# DDW_sch.net
KiCad netlist of a schematic drawn in Altium Designer
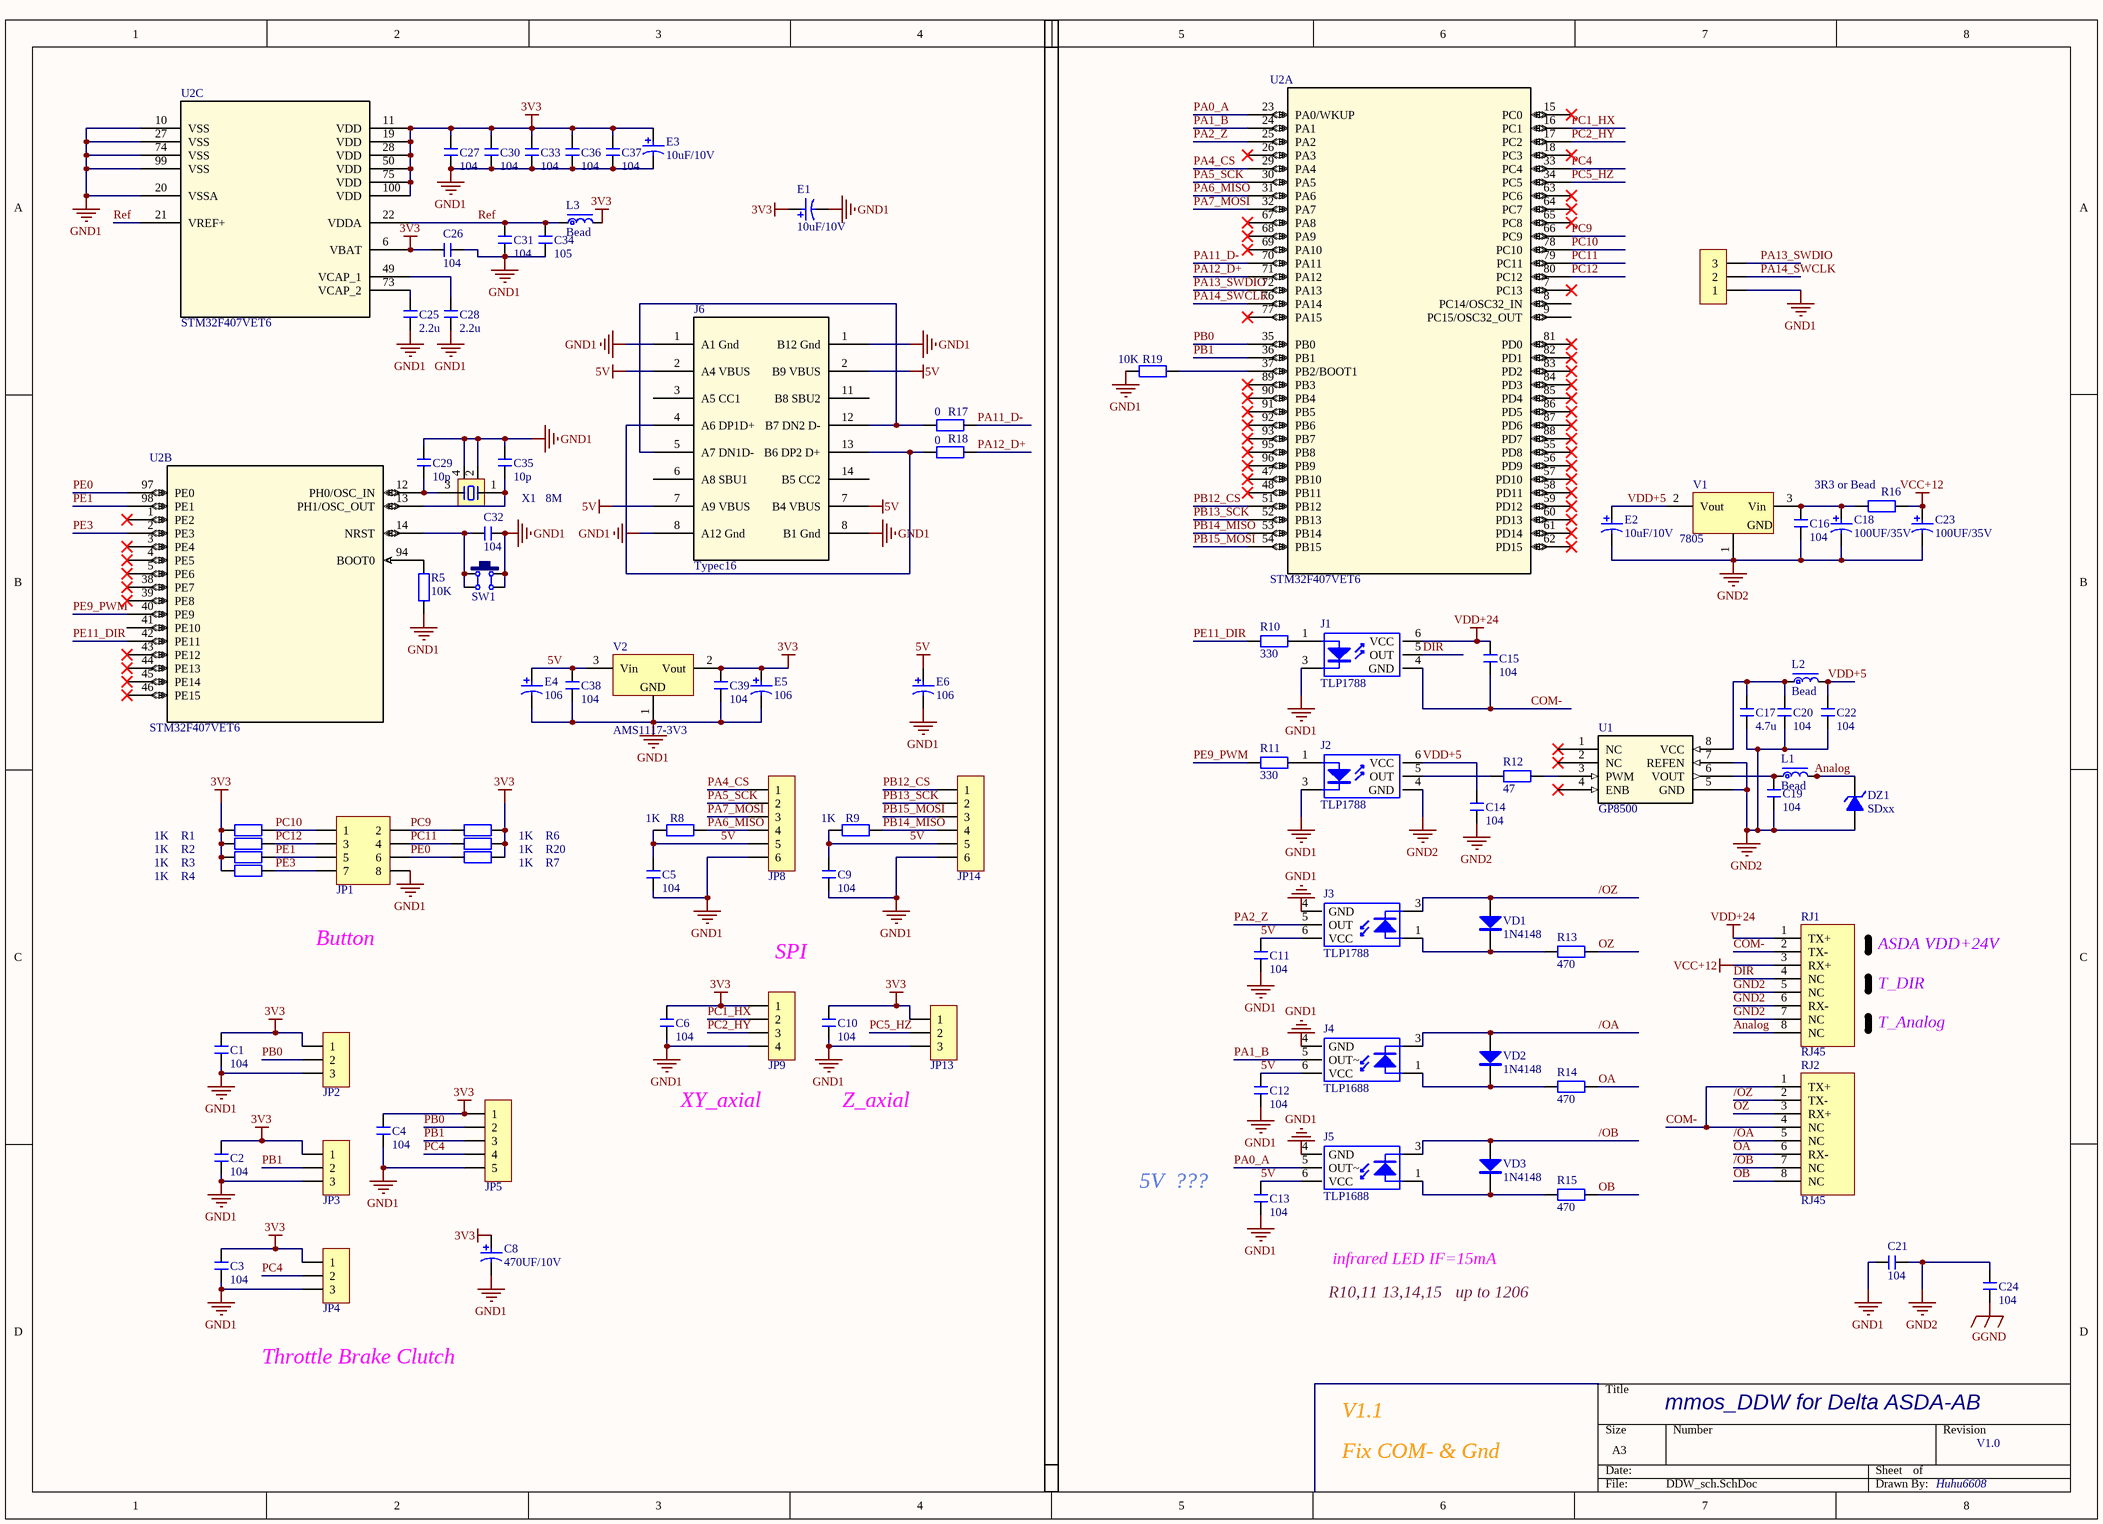
[diagram p0: DDW_sch.SchDoc]

(export (version "E")
  (design (tool "Eeschema 10.0.6"))
  (components
    (comp (ref "C1")
      (value "104")
      (footprint "C 0603")
      (description "瓷片电容-贴片")
      (libsource (lib "A") (part "Cap-CER-SMD"))
    )
    (comp (ref "C2")
      (value "104")
      (footprint "C 0603")
      (description "瓷片电容-贴片")
      (libsource (lib "A") (part "Cap-CER-SMD"))
    )
    (comp (ref "C3")
      (value "104")
      (footprint "C 0603")
      (description "瓷片电容-贴片")
      (libsource (lib "A") (part "Cap-CER-SMD"))
    )
    (comp (ref "C4")
      (value "104")
      (footprint "C 0603")
      (description "瓷片电容-贴片")
      (libsource (lib "A") (part "Cap-CER-SMD"))
    )
    (comp (ref "C5")
      (value "104")
      (footprint "C 0603")
      (description "瓷片电容-贴片")
      (libsource (lib "A") (part "Cap-CER-SMD"))
    )
    (comp (ref "C6")
      (value "104")
      (footprint "C 0603")
      (description "瓷片电容-贴片")
      (libsource (lib "A") (part "Cap-CER-SMD"))
    )
    (comp (ref "C8")
      (value "470UF/10V")
      (footprint "CAP 2.5*6.3*11.2")
      (description "铝电解电容-直插")
      (libsource (lib "A") (part "Cap-AE-RAD"))
    )
    (comp (ref "C9")
      (value "104")
      (footprint "C 0603")
      (description "瓷片电容-贴片")
      (libsource (lib "A") (part "Cap-CER-SMD"))
    )
    (comp (ref "C10")
      (value "104")
      (footprint "C 0603")
      (description "瓷片电容-贴片")
      (libsource (lib "A") (part "Cap-CER-SMD"))
    )
    (comp (ref "C11")
      (value "104")
      (footprint "C 0603")
      (description "瓷片电容-贴片")
      (libsource (lib "A") (part "Cap-CER-SMD"))
    )
    (comp (ref "C12")
      (value "104")
      (footprint "C 0603")
      (description "瓷片电容-贴片")
      (libsource (lib "A") (part "Cap-CER-SMD"))
    )
    (comp (ref "C13")
      (value "104")
      (footprint "C 0603")
      (description "瓷片电容-贴片")
      (libsource (lib "A") (part "Cap-CER-SMD"))
    )
    (comp (ref "C14")
      (value "104")
      (footprint "C 0603")
      (description "瓷片电容-贴片")
      (libsource (lib "A") (part "Cap-CER-SMD"))
    )
    (comp (ref "C15")
      (value "104")
      (footprint "C 0603")
      (description "瓷片电容-贴片")
      (libsource (lib "A") (part "Cap-CER-SMD"))
    )
    (comp (ref "C16")
      (value "104")
      (footprint "C 0603")
      (description "瓷片电容-贴片")
      (libsource (lib "A") (part "Cap-CER-SMD"))
    )
    (comp (ref "C17")
      (value "4.7u")
      (footprint "C 0603")
      (description "瓷片电容-贴片")
      (libsource (lib "A") (part "Cap-CER-SMD"))
    )
    (comp (ref "C18")
      (value "100UF/35V")
      (footprint "CAP 2.5*6.3*11.2")
      (description "铝电解电容-直插")
      (libsource (lib "A") (part "Cap-AE-RAD"))
    )
    (comp (ref "C19")
      (value "104")
      (footprint "C 0603")
      (description "瓷片电容-贴片")
      (libsource (lib "A") (part "Cap-CER-SMD"))
    )
    (comp (ref "C20")
      (value "104")
      (footprint "C 0603")
      (description "瓷片电容-贴片")
      (libsource (lib "A") (part "Cap-CER-SMD"))
    )
    (comp (ref "C21")
      (value "104")
      (footprint "Y")
      (description "瓷片电容-贴片")
      (libsource (lib "A") (part "Cap-CER-SMD"))
    )
    (comp (ref "C22")
      (value "104")
      (footprint "C 0603")
      (description "瓷片电容-贴片")
      (libsource (lib "A") (part "Cap-CER-SMD"))
    )
    (comp (ref "C23")
      (value "100UF/35V")
      (footprint "CAP 2.5*6.3*11.2")
      (description "铝电解电容-直插")
      (libsource (lib "A") (part "Cap-AE-RAD"))
    )
    (comp (ref "C24")
      (value "104")
      (footprint "Y")
      (description "瓷片电容-贴片")
      (libsource (lib "A") (part "Cap-CER-SMD"))
    )
    (comp (ref "C25")
      (value "2.2u")
      (footprint "C 0603")
      (description "瓷片电容-贴片")
      (libsource (lib "A") (part "Cap-CER-SMD"))
    )
    (comp (ref "C26")
      (value "104")
      (footprint "C 0603")
      (description "瓷片电容-贴片")
      (libsource (lib "A") (part "Cap-CER-SMD"))
    )
    (comp (ref "C27")
      (value "104")
      (footprint "C 0603")
      (description "瓷片电容-贴片")
      (libsource (lib "A") (part "Cap-CER-SMD"))
    )
    (comp (ref "C28")
      (value "2.2u")
      (footprint "C 0603")
      (description "瓷片电容-贴片")
      (libsource (lib "A") (part "Cap-CER-SMD"))
    )
    (comp (ref "C29")
      (value "10p")
      (footprint "C 0603")
      (description "瓷片电容-贴片")
      (libsource (lib "A") (part "Cap-CER-SMD"))
    )
    (comp (ref "C30")
      (value "104")
      (footprint "C 0603")
      (description "瓷片电容-贴片")
      (libsource (lib "A") (part "Cap-CER-SMD"))
    )
    (comp (ref "C31")
      (value "104")
      (footprint "C 0603")
      (description "瓷片电容-贴片")
      (libsource (lib "A") (part "Cap-CER-SMD"))
    )
    (comp (ref "C32")
      (value "104")
      (footprint "C 0603")
      (description "瓷片电容-贴片")
      (libsource (lib "A") (part "Cap-CER-SMD"))
    )
    (comp (ref "C33")
      (value "104")
      (footprint "C 0603")
      (description "瓷片电容-贴片")
      (libsource (lib "A") (part "Cap-CER-SMD"))
    )
    (comp (ref "C34")
      (value "105")
      (footprint "C 0603")
      (description "瓷片电容-贴片")
      (libsource (lib "A") (part "Cap-CER-SMD"))
    )
    (comp (ref "C35")
      (value "10p")
      (footprint "C 0603")
      (description "瓷片电容-贴片")
      (libsource (lib "A") (part "Cap-CER-SMD"))
    )
    (comp (ref "C36")
      (value "104")
      (footprint "C 0603")
      (description "瓷片电容-贴片")
      (libsource (lib "A") (part "Cap-CER-SMD"))
    )
    (comp (ref "C37")
      (value "104")
      (footprint "C 0603")
      (description "瓷片电容-贴片")
      (libsource (lib "A") (part "Cap-CER-SMD"))
    )
    (comp (ref "C38")
      (value "104")
      (footprint "C 0603")
      (description "瓷片电容-贴片")
      (libsource (lib "A") (part "Cap-CER-SMD"))
    )
    (comp (ref "C39")
      (value "104")
      (footprint "C 0603")
      (description "瓷片电容-贴片")
      (libsource (lib "A") (part "Cap-CER-SMD"))
    )
    (comp (ref "DZ1")
      (value "SDxx")
      (footprint "SOD-323")
      (description "TVS")
      (fields (field (name "版权归属") "源创客"))
      (libsource (lib "A") (part "SDxx"))
    )
    (comp (ref "E1")
      (value "10uF/10V")
      (footprint "CD B(3528)")
      (description "钽电解电容-贴片")
      (libsource (lib "A") (part "Cap-TAN-SMD"))
    )
    (comp (ref "E2")
      (value "10uF/10V")
      (footprint "CD B(3528)")
      (description "钽电解电容-贴片")
      (libsource (lib "A") (part "Cap-TAN-SMD"))
    )
    (comp (ref "E3")
      (value "10uF/10V")
      (footprint "CD B(3528)")
      (description "钽电解电容-贴片")
      (libsource (lib "A") (part "Cap-TAN-SMD"))
    )
    (comp (ref "E4")
      (value "106")
      (footprint "CD B(3528)")
      (description "钽电解电容-贴片")
      (libsource (lib "A") (part "Cap-TAN-SMD"))
    )
    (comp (ref "E5")
      (value "106")
      (footprint "CD B(3528)")
      (description "钽电解电容-贴片")
      (libsource (lib "A") (part "Cap-TAN-SMD"))
    )
    (comp (ref "E6")
      (value "106")
      (footprint "CD B(3528)")
      (description "钽电解电容-贴片")
      (libsource (lib "A") (part "Cap-TAN-SMD"))
    )
    (comp (ref "J1")
      (value "TLP1788")
      (footprint "SOP5")
      (description "光耦")
      (fields (field (name "版权归属") "源创客"))
      (libsource (lib "A") (part "TLP1788"))
    )
    (comp (ref "J2")
      (value "TLP1788")
      (footprint "SOP5")
      (description "光耦")
      (fields (field (name "版权归属") "源创客"))
      (libsource (lib "A") (part "TLP1788"))
    )
    (comp (ref "J3")
      (value "TLP1788")
      (footprint "SOP5")
      (description "光耦")
      (fields (field (name "版权归属") "源创客"))
      (libsource (lib "Miscellaneous Devices") (part "TLP1788"))
    )
    (comp (ref "J4")
      (value "TLP1688")
      (footprint "SOP5")
      (description "光耦")
      (fields (field (name "版权归属") "源创客"))
      (libsource (lib "A") (part "TLP1688"))
    )
    (comp (ref "J5")
      (value "TLP1688")
      (footprint "SOP5")
      (description "光耦")
      (fields (field (name "版权归属") "源创客"))
      (libsource (lib "A") (part "TLP1688"))
    )
    (comp (ref "J6") (value "Typec16") (footprint "typec 16p") (libsource (lib "A") (part "Typec16")))
    (comp (ref "JP1")
      (value "Header 4X2")
      (footprint "HDR-4X2")
      (description "4*2P接插件")
      (fields (field (name "版权归属") "源创客"))
      (libsource (lib "A") (part "Header 4X2"))
    )
    (comp (ref "JP2")
      (value "HDR-1X3")
      (footprint "HDR-1X3")
      (description "3P接插件")
      (fields (field (name "版权归属") "源创客"))
      (libsource (lib "A") (part "Header 3"))
    )
    (comp (ref "JP3")
      (value "HDR-1X3")
      (footprint "HDR-1X3")
      (description "3P接插件")
      (fields (field (name "版权归属") "源创客"))
      (libsource (lib "A") (part "Header 3"))
    )
    (comp (ref "JP4")
      (value "HDR-1X3")
      (footprint "HDR-1X3")
      (description "3P接插件")
      (fields (field (name "版权归属") "源创客"))
      (libsource (lib "A") (part "Header 3"))
    )
    (comp (ref "JP5")
      (value "HDR-1X5")
      (footprint "HDR-1X5")
      (description "5P接插件")
      (fields (field (name "版权归属") "源创客"))
      (libsource (lib "A") (part "Header 5"))
    )
    (comp (ref "JP6")
      (value "HDR-1X3")
      (footprint "HDR-1X3")
      (description "3P接插件")
      (fields (field (name "版权归属") "源创客"))
      (libsource (lib "") (part "Header 3_1"))
    )
    (comp (ref "JP8")
      (value "HDR-1X6")
      (footprint "HDR-1X6")
      (description "6P接插件")
      (fields (field (name "版权归属") "源创客"))
      (libsource (lib "A") (part "Header 6"))
    )
    (comp (ref "JP9")
      (value "HDR-1X4")
      (footprint "HDR-1X4")
      (description "4P接插件")
      (fields (field (name "版权归属") "源创客"))
      (libsource (lib "A") (part "Header 4"))
    )
    (comp (ref "JP13")
      (value "HDR-1X3")
      (footprint "HDR-1X3")
      (description "3P接插件")
      (fields (field (name "版权归属") "源创客"))
      (libsource (lib "A") (part "Header 3"))
    )
    (comp (ref "JP14")
      (value "HDR-1X6")
      (footprint "HDR-1X6")
      (description "6P接插件")
      (fields (field (name "版权归属") "源创客"))
      (libsource (lib "A") (part "Header 6"))
    )
    (comp (ref "L1") (value "Bead") (footprint "L 0805") (libsource (lib "A") (part "Bead")))
    (comp (ref "L2") (value "Bead") (footprint "L 0805") (libsource (lib "A") (part "Ind-Beads-SMD")))
    (comp (ref "L3") (value "Bead") (footprint "L 0603") (libsource (lib "A") (part "Bead")))
    (comp (ref "R1")
      (value "1K")
      (footprint "Res-SMD-0603")
      (description "固定电阻器-贴片")
      (libsource (lib "A") (part "Res-Fixed-SMD"))
    )
    (comp (ref "R2")
      (value "1K")
      (footprint "Res-SMD-0603")
      (description "固定电阻器-贴片")
      (libsource (lib "A") (part "Res-Fixed-SMD"))
    )
    (comp (ref "R3")
      (value "1K")
      (footprint "Res-SMD-0603")
      (description "固定电阻器-贴片")
      (libsource (lib "A") (part "Res-Fixed-SMD"))
    )
    (comp (ref "R4")
      (value "1K")
      (footprint "Res-SMD-0603")
      (description "固定电阻器-贴片")
      (libsource (lib "A") (part "Res-Fixed-SMD"))
    )
    (comp (ref "R5")
      (value "10K")
      (footprint "Res-SMD-0603")
      (description "固定电阻器-贴片")
      (libsource (lib "A") (part "Res-Fixed-SMD"))
    )
    (comp (ref "R6")
      (value "1K")
      (footprint "Res-SMD-0603")
      (description "固定电阻器-贴片")
      (libsource (lib "A") (part "Res-Fixed-SMD"))
    )
    (comp (ref "R7")
      (value "1K")
      (footprint "Res-SMD-0603")
      (description "固定电阻器-贴片")
      (libsource (lib "A") (part "Res-Fixed-SMD"))
    )
    (comp (ref "R8")
      (value "1K")
      (footprint "Res-SMD-0603")
      (description "固定电阻器-贴片")
      (libsource (lib "A") (part "Res-Fixed-SMD"))
    )
    (comp (ref "R9")
      (value "1K")
      (footprint "Res-SMD-0603")
      (description "固定电阻器-贴片")
      (libsource (lib "A") (part "Res-Fixed-SMD"))
    )
    (comp (ref "R10")
      (value "330")
      (footprint "Res-SMD-1206")
      (description "固定电阻器-贴片")
      (libsource (lib "A") (part "Res-Fixed-SMD"))
    )
    (comp (ref "R11")
      (value "330")
      (footprint "Res-SMD-1206")
      (description "固定电阻器-贴片")
      (libsource (lib "A") (part "Res-Fixed-SMD"))
    )
    (comp (ref "R12")
      (value "47")
      (footprint "Res-SMD-0603")
      (description "固定电阻器-贴片")
      (libsource (lib "A") (part "Res-Fixed-SMD"))
    )
    (comp (ref "R13")
      (value "470")
      (footprint "Res-SMD-1206")
      (description "固定电阻器-贴片")
      (libsource (lib "A") (part "Res-Fixed-SMD"))
    )
    (comp (ref "R14")
      (value "470")
      (footprint "Res-SMD-1206")
      (description "固定电阻器-贴片")
      (libsource (lib "A") (part "Res-Fixed-SMD"))
    )
    (comp (ref "R15")
      (value "470")
      (footprint "Res-SMD-1206")
      (description "固定电阻器-贴片")
      (libsource (lib "A") (part "Res-Fixed-SMD"))
    )
    (comp (ref "R16")
      (value "3R3 or Bead")
      (footprint "Res-SMD-1206")
      (description "固定电阻器-贴片")
      (libsource (lib "A") (part "Res-Fixed-SMD"))
    )
    (comp (ref "R17")
      (value "0")
      (footprint "Res-SMD-0603")
      (description "固定电阻器-贴片")
      (libsource (lib "A") (part "Res-Fixed-SMD"))
    )
    (comp (ref "R18")
      (value "0")
      (footprint "Res-SMD-0603")
      (description "固定电阻器-贴片")
      (libsource (lib "A") (part "Res-Fixed-SMD"))
    )
    (comp (ref "R19")
      (value "10K")
      (footprint "Res-SMD-0603")
      (description "固定电阻器-贴片")
      (libsource (lib "A") (part "Res-Fixed-SMD"))
    )
    (comp (ref "R20")
      (value "1K")
      (footprint "Res-SMD-0603")
      (description "固定电阻器-贴片")
      (libsource (lib "A") (part "Res-Fixed-SMD"))
    )
    (comp (ref "RJ1")
      (value "RJ45")
      (footprint "RJ45-2")
      (description "以太网接口")
      (fields (field (name "版权归属") "源创客"))
      (libsource (lib "A") (part "RJ45"))
    )
    (comp (ref "RJ2")
      (value "RJ45")
      (footprint "RJ45-2")
      (description "以太网接口")
      (fields (field (name "版权归属") "源创客"))
      (libsource (lib "A") (part "RJ45"))
    )
    (comp (ref "SW1")
      (value "6x6x5")
      (footprint "TSW DIP-6*6*5")
      (description "直插6x6轻触开关")
      (fields (field (name "版权归属") "源创客"))
      (libsource (lib "A") (part "TSW DIP-6x6"))
    )
    (comp (ref "U1")
      (value "GP8500")
      (footprint "SOP8_N")
      (description "PAC")
      (fields (field (name "MANUFACTURER_PART_NUMBER") "ltc2644ims-l12#pbf"))
      (libsource (lib "A") (part "GP8500"))
    )
    (comp (ref "U2")
      (value "STM32F407VET6")
      (footprint "TQFP100 14x14_N")
      (description "No Description Available")
      (fields (field (name "COPYRIGHT") "Copyright (C) 2018 Accelerated Designs. All rights reserved"))
      (libsource (lib "A") (part "STM32F407VET6"))
    )
    (comp (ref "V1")
      (value "7805")
      (footprint "SOT89_N")
      (description "三端稳压芯片")
      (fields (field (name "版权归属") "源创客"))
      (libsource (lib "") (part "78LDO_1"))
    )
    (comp (ref "V2")
      (value "AMS1117-3V3")
      (footprint "SOT223_N")
      (description "三端稳压芯片")
      (fields (field (name "版权归属") "源创客"))
      (libsource (lib "A") (part "78LDO"))
    )
    (comp (ref "VD1")
      (value "1N4148")
      (footprint "MINI_MELF (LL34)")
      (description "高速开关二极管")
      (fields (field (name "版权归属") "源创客"))
      (libsource (lib "A") (part "1N4148"))
    )
    (comp (ref "VD2")
      (value "1N4148")
      (footprint "MINI_MELF (LL34)")
      (description "高速开关二极管")
      (fields (field (name "版权归属") "源创客"))
      (libsource (lib "A") (part "1N4148"))
    )
    (comp (ref "VD3")
      (value "1N4148")
      (footprint "MINI_MELF (LL34)")
      (description "高速开关二极管")
      (fields (field (name "版权归属") "源创客"))
      (libsource (lib "A") (part "1N4148"))
    )
    (comp (ref "X1")
      (value "8M")
      (footprint "XTAL-3225")
      (description "4脚晶振")
      (fields (field (name "版权归属") "源创客"))
      (libsource (lib "保险丝-晶振") (part "XTAL-4"))
    )
  )
  (nets
    (net (code "1") (name "/Analog") (class "Default")
      (node (ref "DZ1") (pin "2") (pinfunction "K_2") (pintype "passive"))
      (node (ref "L1") (pin "2") (pinfunction "2_2") (pintype "passive"))
      (node (ref "RJ1") (pin "8") (pinfunction "NC_8") (pintype "passive"))
    )
    (net (code "2") (name "/COM-") (class "Default")
      (node (ref "C15") (pin "2") (pinfunction "2_2") (pintype "passive"))
      (node (ref "J1") (pin "4") (pinfunction "GND_4") (pintype "passive"))
      (node (ref "RJ1") (pin "2") (pinfunction "TX-_2") (pintype "passive"))
      (node (ref "RJ2") (pin "1") (pinfunction "TX+_1") (pintype "passive"))
      (node (ref "RJ2") (pin "4") (pinfunction "NC_4") (pintype "passive"))
    )
    (net (code "3") (name "/DIR") (class "Default")
      (node (ref "J1") (pin "5") (pinfunction "OUT_5") (pintype "passive"))
      (node (ref "RJ1") (pin "4") (pinfunction "NC_4") (pintype "passive"))
    )
    (net (code "4") (name "/OA") (class "Default")
      (node (ref "R14") (pin "2") (pinfunction "2_2") (pintype "passive"))
      (node (ref "RJ2") (pin "6") (pinfunction "RX-_6") (pintype "passive"))
    )
    (net (code "5") (name "/OB") (class "Default")
      (node (ref "R15") (pin "2") (pinfunction "2_2") (pintype "passive"))
      (node (ref "RJ2") (pin "8") (pinfunction "NC_8") (pintype "passive"))
    )
    (net (code "6") (name "/OZ") (class "Default")
      (node (ref "R13") (pin "2") (pinfunction "2_2") (pintype "passive"))
      (node (ref "RJ2") (pin "3") (pinfunction "RX+_3") (pintype "passive"))
    )
    (net (code "7") (name "/PA0_A") (class "Default")
      (node (ref "J5") (pin "5") (pinfunction "OUT~_5") (pintype "passive"))
      (node (ref "U2") (pin "23") (pinfunction "PA0/WKUP_23") (pintype "bidirectional"))
    )
    (net (code "8") (name "/PA1_B") (class "Default")
      (node (ref "J4") (pin "5") (pinfunction "OUT~_5") (pintype "passive"))
      (node (ref "U2") (pin "24") (pinfunction "PA1_24") (pintype "bidirectional"))
    )
    (net (code "9") (name "/PA2_Z") (class "Default")
      (node (ref "J3") (pin "5") (pinfunction "OUT_5") (pintype "passive"))
      (node (ref "U2") (pin "25") (pinfunction "PA2_25") (pintype "bidirectional"))
    )
    (net (code "10") (name "/PA4_CS") (class "Default")
      (node (ref "JP8") (pin "1") (pinfunction "1_1") (pintype "passive"))
      (node (ref "U2") (pin "29") (pinfunction "PA4_29") (pintype "bidirectional"))
    )
    (net (code "11") (name "/PA5_SCK") (class "Default")
      (node (ref "JP8") (pin "2") (pinfunction "2_2") (pintype "passive"))
      (node (ref "U2") (pin "30") (pinfunction "PA5_30") (pintype "bidirectional"))
    )
    (net (code "12") (name "/PA6_MISO") (class "Default")
      (node (ref "JP8") (pin "4") (pinfunction "4_4") (pintype "passive"))
      (node (ref "R8") (pin "1") (pinfunction "1_1") (pintype "passive"))
      (node (ref "U2") (pin "31") (pinfunction "PA6_31") (pintype "bidirectional"))
    )
    (net (code "13") (name "/PA7_MOSI") (class "Default")
      (node (ref "JP8") (pin "3") (pinfunction "3_3") (pintype "passive"))
      (node (ref "U2") (pin "32") (pinfunction "PA7_32") (pintype "bidirectional"))
    )
    (net (code "14") (name "/PA11_D-") (class "Default")
      (node (ref "R17") (pin "1") (pinfunction "1_1") (pintype "passive"))
      (node (ref "U2") (pin "70") (pinfunction "PA11_70") (pintype "bidirectional"))
    )
    (net (code "15") (name "/PA12_D+") (class "Default")
      (node (ref "R18") (pin "1") (pinfunction "1_1") (pintype "passive"))
      (node (ref "U2") (pin "71") (pinfunction "PA12_71") (pintype "bidirectional"))
    )
    (net (code "16") (name "/PA13_SWDIO") (class "Default")
      (node (ref "JP6") (pin "3") (pinfunction "3_3") (pintype "passive"))
      (node (ref "U2") (pin "72") (pinfunction "PA13_72") (pintype "bidirectional"))
    )
    (net (code "17") (name "/PA14_SWCLK") (class "Default")
      (node (ref "JP6") (pin "2") (pinfunction "2_2") (pintype "passive"))
      (node (ref "U2") (pin "76") (pinfunction "PA14_76") (pintype "bidirectional"))
    )
    (net (code "18") (name "/PB0") (class "Default")
      (node (ref "JP2") (pin "2") (pinfunction "2_2") (pintype "passive"))
      (node (ref "JP5") (pin "2") (pinfunction "2_2") (pintype "passive"))
      (node (ref "U2") (pin "35") (pinfunction "PB0_35") (pintype "bidirectional"))
    )
    (net (code "19") (name "/PB1") (class "Default")
      (node (ref "JP3") (pin "2") (pinfunction "2_2") (pintype "passive"))
      (node (ref "JP5") (pin "3") (pinfunction "3_3") (pintype "passive"))
      (node (ref "U2") (pin "36") (pinfunction "PB1_36") (pintype "bidirectional"))
    )
    (net (code "20") (name "/PB12_CS") (class "Default")
      (node (ref "JP14") (pin "1") (pinfunction "1_1") (pintype "passive"))
      (node (ref "U2") (pin "51") (pinfunction "PB12_51") (pintype "bidirectional"))
    )
    (net (code "21") (name "/PB13_SCK") (class "Default")
      (node (ref "JP14") (pin "2") (pinfunction "2_2") (pintype "passive"))
      (node (ref "U2") (pin "52") (pinfunction "PB13_52") (pintype "bidirectional"))
    )
    (net (code "22") (name "/PB14_MISO") (class "Default")
      (node (ref "JP14") (pin "4") (pinfunction "4_4") (pintype "passive"))
      (node (ref "R9") (pin "1") (pinfunction "1_1") (pintype "passive"))
      (node (ref "U2") (pin "53") (pinfunction "PB14_53") (pintype "bidirectional"))
    )
    (net (code "23") (name "/PB15_MOSI") (class "Default")
      (node (ref "JP14") (pin "3") (pinfunction "3_3") (pintype "passive"))
      (node (ref "U2") (pin "54") (pinfunction "PB15_54") (pintype "bidirectional"))
    )
    (net (code "24") (name "/PC1_HX") (class "Default")
      (node (ref "JP9") (pin "2") (pinfunction "2_2") (pintype "passive"))
      (node (ref "U2") (pin "16") (pinfunction "PC1_16") (pintype "bidirectional"))
    )
    (net (code "25") (name "/PC2_HY") (class "Default")
      (node (ref "JP9") (pin "3") (pinfunction "3_3") (pintype "passive"))
      (node (ref "U2") (pin "17") (pinfunction "PC2_17") (pintype "bidirectional"))
    )
    (net (code "26") (name "/PC4") (class "Default")
      (node (ref "JP4") (pin "2") (pinfunction "2_2") (pintype "passive"))
      (node (ref "JP5") (pin "4") (pinfunction "4_4") (pintype "passive"))
      (node (ref "U2") (pin "33") (pinfunction "PC4_33") (pintype "bidirectional"))
    )
    (net (code "27") (name "/PC5_HZ") (class "Default")
      (node (ref "JP13") (pin "2") (pinfunction "2_2") (pintype "passive"))
      (node (ref "U2") (pin "34") (pinfunction "PC5_34") (pintype "bidirectional"))
    )
    (net (code "28") (name "/PC9") (class "Default")
      (node (ref "JP1") (pin "2") (pinfunction "2_2") (pintype "passive"))
      (node (ref "R6") (pin "2") (pinfunction "2_2") (pintype "passive"))
      (node (ref "U2") (pin "66") (pinfunction "PC9_66") (pintype "bidirectional"))
    )
    (net (code "29") (name "/PC10") (class "Default")
      (node (ref "JP1") (pin "1") (pinfunction "1_1") (pintype "passive"))
      (node (ref "R1") (pin "1") (pinfunction "1_1") (pintype "passive"))
      (node (ref "U2") (pin "78") (pinfunction "PC10_78") (pintype "bidirectional"))
    )
    (net (code "30") (name "/PC11") (class "Default")
      (node (ref "JP1") (pin "4") (pinfunction "4_4") (pintype "passive"))
      (node (ref "R20") (pin "2") (pinfunction "2_2") (pintype "passive"))
      (node (ref "U2") (pin "79") (pinfunction "PC11_79") (pintype "bidirectional"))
    )
    (net (code "31") (name "/PC12") (class "Default")
      (node (ref "JP1") (pin "3") (pinfunction "3_3") (pintype "passive"))
      (node (ref "R2") (pin "1") (pinfunction "1_1") (pintype "passive"))
      (node (ref "U2") (pin "80") (pinfunction "PC12_80") (pintype "bidirectional"))
    )
    (net (code "32") (name "/PE0") (class "Default")
      (node (ref "JP1") (pin "6") (pinfunction "6_6") (pintype "passive"))
      (node (ref "R7") (pin "2") (pinfunction "2_2") (pintype "passive"))
      (node (ref "U2") (pin "97") (pinfunction "PE0_97") (pintype "bidirectional"))
    )
    (net (code "33") (name "/PE1") (class "Default")
      (node (ref "JP1") (pin "5") (pinfunction "5_5") (pintype "passive"))
      (node (ref "R3") (pin "1") (pinfunction "1_1") (pintype "passive"))
      (node (ref "U2") (pin "98") (pinfunction "PE1_98") (pintype "bidirectional"))
    )
    (net (code "34") (name "/PE3") (class "Default")
      (node (ref "JP1") (pin "7") (pinfunction "7_7") (pintype "passive"))
      (node (ref "R4") (pin "1") (pinfunction "1_1") (pintype "passive"))
      (node (ref "U2") (pin "2") (pinfunction "PE3_2") (pintype "bidirectional"))
    )
    (net (code "35") (name "/PE9_PWM") (class "Default")
      (node (ref "R11") (pin "1") (pinfunction "1_1") (pintype "passive"))
      (node (ref "U2") (pin "40") (pinfunction "PE9_40") (pintype "bidirectional"))
    )
    (net (code "36") (name "/PE11_DIR") (class "Default")
      (node (ref "R10") (pin "1") (pinfunction "1_1") (pintype "passive"))
      (node (ref "U2") (pin "42") (pinfunction "PE11_42") (pintype "bidirectional"))
    )
    (net (code "37") (name "/Ref") (class "Default")
      (node (ref "C31") (pin "1") (pinfunction "1_1") (pintype "passive"))
      (node (ref "C34") (pin "1") (pinfunction "1_1") (pintype "passive"))
      (node (ref "L3") (pin "1") (pinfunction "1_1") (pintype "passive"))
      (node (ref "U2") (pin "21") (pinfunction "VREF+_21") (pintype "power_in"))
      (node (ref "U2") (pin "22") (pinfunction "VDDA_22") (pintype "power_in"))
    )
    (net (code "38") (name "/VDD+5") (class "Default")
      (node (ref "C14") (pin "1") (pinfunction "1_1") (pintype "passive"))
      (node (ref "C22") (pin "1") (pinfunction "1_1") (pintype "passive"))
      (node (ref "E2") (pin "A") (pinfunction "A_A") (pintype "passive"))
      (node (ref "J2") (pin "6") (pinfunction "VCC_6") (pintype "passive"))
      (node (ref "L2") (pin "2") (pinfunction "2_2") (pintype "passive"))
      (node (ref "V1") (pin "2") (pinfunction "Vout_2") (pintype "passive"))
    )
    (net (code "39") (name "/{slash}OA") (class "Default")
      (node (ref "J4") (pin "3") (pinfunction "K_3") (pintype "passive"))
      (node (ref "RJ2") (pin "5") (pinfunction "NC_5") (pintype "passive"))
      (node (ref "VD2") (pin "1") (pinfunction "A_1") (pintype "passive"))
    )
    (net (code "40") (name "/{slash}OB") (class "Default")
      (node (ref "J5") (pin "3") (pinfunction "K_3") (pintype "passive"))
      (node (ref "RJ2") (pin "7") (pinfunction "NC_7") (pintype "passive"))
      (node (ref "VD3") (pin "1") (pinfunction "A_1") (pintype "passive"))
    )
    (net (code "41") (name "/{slash}OZ") (class "Default")
      (node (ref "J3") (pin "3") (pinfunction "K_3") (pintype "passive"))
      (node (ref "RJ2") (pin "2") (pinfunction "TX-_2") (pintype "passive"))
      (node (ref "VD1") (pin "1") (pinfunction "A_1") (pintype "passive"))
    )
    (net (code "42") (name "3V3") (class "Default")
      (node (ref "C1") (pin "1") (pinfunction "1_1") (pintype "passive"))
      (node (ref "C10") (pin "1") (pinfunction "1_1") (pintype "passive"))
      (node (ref "C2") (pin "1") (pinfunction "1_1") (pintype "passive"))
      (node (ref "C26") (pin "2") (pinfunction "2_2") (pintype "passive"))
      (node (ref "C27") (pin "2") (pinfunction "2_2") (pintype "passive"))
      (node (ref "C3") (pin "1") (pinfunction "1_1") (pintype "passive"))
      (node (ref "C30") (pin "2") (pinfunction "2_2") (pintype "passive"))
      (node (ref "C33") (pin "2") (pinfunction "2_2") (pintype "passive"))
      (node (ref "C36") (pin "2") (pinfunction "2_2") (pintype "passive"))
      (node (ref "C37") (pin "2") (pinfunction "2_2") (pintype "passive"))
      (node (ref "C39") (pin "1") (pinfunction "1_1") (pintype "passive"))
      (node (ref "C4") (pin "1") (pinfunction "1_1") (pintype "passive"))
      (node (ref "C6") (pin "1") (pinfunction "1_1") (pintype "passive"))
      (node (ref "C8") (pin "A") (pinfunction "A_A") (pintype "passive"))
      (node (ref "E1") (pin "A") (pinfunction "A_A") (pintype "passive"))
      (node (ref "E3") (pin "A") (pinfunction "A_A") (pintype "passive"))
      (node (ref "E5") (pin "A") (pinfunction "A_A") (pintype "passive"))
      (node (ref "JP13") (pin "1") (pinfunction "1_1") (pintype "passive"))
      (node (ref "JP2") (pin "1") (pinfunction "1_1") (pintype "passive"))
      (node (ref "JP3") (pin "1") (pinfunction "1_1") (pintype "passive"))
      (node (ref "JP4") (pin "1") (pinfunction "1_1") (pintype "passive"))
      (node (ref "JP5") (pin "1") (pinfunction "1_1") (pintype "passive"))
      (node (ref "JP9") (pin "1") (pinfunction "1_1") (pintype "passive"))
      (node (ref "L3") (pin "2") (pinfunction "2_2") (pintype "passive"))
      (node (ref "R1") (pin "2") (pinfunction "2_2") (pintype "passive"))
      (node (ref "R2") (pin "2") (pinfunction "2_2") (pintype "passive"))
      (node (ref "R20") (pin "1") (pinfunction "1_1") (pintype "passive"))
      (node (ref "R3") (pin "2") (pinfunction "2_2") (pintype "passive"))
      (node (ref "R4") (pin "2") (pinfunction "2_2") (pintype "passive"))
      (node (ref "R6") (pin "1") (pinfunction "1_1") (pintype "passive"))
      (node (ref "R7") (pin "1") (pinfunction "1_1") (pintype "passive"))
      (node (ref "U2") (pin "100") (pinfunction "VDD_100") (pintype "power_in"))
      (node (ref "U2") (pin "11") (pinfunction "VDD_11") (pintype "power_in"))
      (node (ref "U2") (pin "19") (pinfunction "VDD_19") (pintype "power_in"))
      (node (ref "U2") (pin "28") (pinfunction "VDD_28") (pintype "power_in"))
      (node (ref "U2") (pin "50") (pinfunction "VDD_50") (pintype "power_in"))
      (node (ref "U2") (pin "6") (pinfunction "VBAT_6") (pintype "power_in"))
      (node (ref "U2") (pin "75") (pinfunction "VDD_75") (pintype "power_in"))
      (node (ref "V2") (pin "2") (pinfunction "Vout_2") (pintype "passive"))
    )
    (net (code "43") (name "5V") (class "Default")
      (node (ref "C11") (pin "1") (pinfunction "1_1") (pintype "passive"))
      (node (ref "C12") (pin "1") (pinfunction "1_1") (pintype "passive"))
      (node (ref "C13") (pin "1") (pinfunction "1_1") (pintype "passive"))
      (node (ref "C38") (pin "1") (pinfunction "1_1") (pintype "passive"))
      (node (ref "C5") (pin "1") (pinfunction "1_1") (pintype "passive"))
      (node (ref "C9") (pin "1") (pinfunction "1_1") (pintype "passive"))
      (node (ref "E4") (pin "A") (pinfunction "A_A") (pintype "passive"))
      (node (ref "E6") (pin "A") (pinfunction "A_A") (pintype "passive"))
      (node (ref "J3") (pin "6") (pinfunction "VCC_6") (pintype "passive"))
      (node (ref "J4") (pin "6") (pinfunction "VCC_6") (pintype "passive"))
      (node (ref "J5") (pin "6") (pinfunction "VCC_6") (pintype "passive"))
      (node (ref "J6") (pin "2") (pinfunction "B9_VBUS_2") (pintype "passive"))
      (node (ref "J6") (pin "7") (pinfunction "A9_VBUS_7") (pintype "passive"))
      (node (ref "JP14") (pin "5") (pinfunction "5_5") (pintype "passive"))
      (node (ref "JP8") (pin "5") (pinfunction "5_5") (pintype "passive"))
      (node (ref "R8") (pin "2") (pinfunction "2_2") (pintype "passive"))
      (node (ref "R9") (pin "2") (pinfunction "2_2") (pintype "passive"))
      (node (ref "V2") (pin "3") (pinfunction "Vin_3") (pintype "passive"))
    )
    (net (code "44") (name "GGND") (class "Default")
      (node (ref "C24") (pin "2") (pinfunction "2_2") (pintype "passive"))
    )
    (net (code "45") (name "GND1") (class "Default")
      (node (ref "C1") (pin "2") (pinfunction "2_2") (pintype "passive"))
      (node (ref "C10") (pin "2") (pinfunction "2_2") (pintype "passive"))
      (node (ref "C11") (pin "2") (pinfunction "2_2") (pintype "passive"))
      (node (ref "C12") (pin "2") (pinfunction "2_2") (pintype "passive"))
      (node (ref "C13") (pin "2") (pinfunction "2_2") (pintype "passive"))
      (node (ref "C2") (pin "2") (pinfunction "2_2") (pintype "passive"))
      (node (ref "C21") (pin "1") (pinfunction "1_1") (pintype "passive"))
      (node (ref "C25") (pin "1") (pinfunction "1_1") (pintype "passive"))
      (node (ref "C26") (pin "1") (pinfunction "1_1") (pintype "passive"))
      (node (ref "C27") (pin "1") (pinfunction "1_1") (pintype "passive"))
      (node (ref "C28") (pin "1") (pinfunction "1_1") (pintype "passive"))
      (node (ref "C29") (pin "2") (pinfunction "2_2") (pintype "passive"))
      (node (ref "C3") (pin "2") (pinfunction "2_2") (pintype "passive"))
      (node (ref "C30") (pin "1") (pinfunction "1_1") (pintype "passive"))
      (node (ref "C31") (pin "2") (pinfunction "2_2") (pintype "passive"))
      (node (ref "C32") (pin "2") (pinfunction "2_2") (pintype "passive"))
      (node (ref "C33") (pin "1") (pinfunction "1_1") (pintype "passive"))
      (node (ref "C34") (pin "2") (pinfunction "2_2") (pintype "passive"))
      (node (ref "C35") (pin "2") (pinfunction "2_2") (pintype "passive"))
      (node (ref "C36") (pin "1") (pinfunction "1_1") (pintype "passive"))
      (node (ref "C37") (pin "1") (pinfunction "1_1") (pintype "passive"))
      (node (ref "C38") (pin "2") (pinfunction "2_2") (pintype "passive"))
      (node (ref "C39") (pin "2") (pinfunction "2_2") (pintype "passive"))
      (node (ref "C4") (pin "2") (pinfunction "2_2") (pintype "passive"))
      (node (ref "C5") (pin "2") (pinfunction "2_2") (pintype "passive"))
      (node (ref "C6") (pin "2") (pinfunction "2_2") (pintype "passive"))
      (node (ref "C8") (pin "K") (pinfunction "K_K") (pintype "passive"))
      (node (ref "C9") (pin "2") (pinfunction "2_2") (pintype "passive"))
      (node (ref "E1") (pin "K") (pinfunction "K_K") (pintype "passive"))
      (node (ref "E3") (pin "K") (pinfunction "K_K") (pintype "passive"))
      (node (ref "E4") (pin "K") (pinfunction "K_K") (pintype "passive"))
      (node (ref "E5") (pin "K") (pinfunction "K_K") (pintype "passive"))
      (node (ref "E6") (pin "K") (pinfunction "K_K") (pintype "passive"))
      (node (ref "J1") (pin "3") (pinfunction "K_3") (pintype "passive"))
      (node (ref "J2") (pin "3") (pinfunction "K_3") (pintype "passive"))
      (node (ref "J3") (pin "4") (pinfunction "GND_4") (pintype "passive"))
      (node (ref "J4") (pin "4") (pinfunction "GND_4") (pintype "passive"))
      (node (ref "J5") (pin "4") (pinfunction "GND_4") (pintype "passive"))
      (node (ref "J6") (pin "1") (pinfunction "A1_Gnd_1") (pintype "passive"))
      (node (ref "J6") (pin "8") (pinfunction "A12_Gnd_8") (pintype "passive"))
      (node (ref "JP1") (pin "8") (pinfunction "8_8") (pintype "passive"))
      (node (ref "JP13") (pin "3") (pinfunction "3_3") (pintype "passive"))
      (node (ref "JP14") (pin "6") (pinfunction "6_6") (pintype "passive"))
      (node (ref "JP2") (pin "3") (pinfunction "3_3") (pintype "passive"))
      (node (ref "JP3") (pin "3") (pinfunction "3_3") (pintype "passive"))
      (node (ref "JP4") (pin "3") (pinfunction "3_3") (pintype "passive"))
      (node (ref "JP5") (pin "5") (pinfunction "5_5") (pintype "passive"))
      (node (ref "JP6") (pin "1") (pinfunction "1_1") (pintype "passive"))
      (node (ref "JP8") (pin "6") (pinfunction "6_6") (pintype "passive"))
      (node (ref "JP9") (pin "4") (pinfunction "4_4") (pintype "passive"))
      (node (ref "R19") (pin "2") (pinfunction "2_2") (pintype "passive"))
      (node (ref "R5") (pin "2") (pinfunction "2_2") (pintype "passive"))
      (node (ref "SW1") (pin "2") (pinfunction "2_2") (pintype "passive"))
      (node (ref "SW1") (pin "3") (pinfunction "3_3") (pintype "passive"))
      (node (ref "U2") (pin "10") (pinfunction "VSS_10") (pintype "power_in"))
      (node (ref "U2") (pin "20") (pinfunction "VSSA_20") (pintype "power_in"))
      (node (ref "U2") (pin "27") (pinfunction "VSS_27") (pintype "power_in"))
      (node (ref "U2") (pin "74") (pinfunction "VSS_74") (pintype "power_in"))
      (node (ref "U2") (pin "99") (pinfunction "VSS_99") (pintype "power_in"))
      (node (ref "V2") (pin "1") (pinfunction "GND_1") (pintype "passive"))
      (node (ref "X1") (pin "2") (pinfunction "2_2") (pintype "passive"))
      (node (ref "X1") (pin "4") (pinfunction "4_4") (pintype "passive"))
    )
    (net (code "46") (name "GND2") (class "Default")
      (node (ref "C14") (pin "2") (pinfunction "2_2") (pintype "passive"))
      (node (ref "C16") (pin "2") (pinfunction "2_2") (pintype "passive"))
      (node (ref "C17") (pin "2") (pinfunction "2_2") (pintype "passive"))
      (node (ref "C18") (pin "K") (pinfunction "K_K") (pintype "passive"))
      (node (ref "C19") (pin "2") (pinfunction "2_2") (pintype "passive"))
      (node (ref "C20") (pin "2") (pinfunction "2_2") (pintype "passive"))
      (node (ref "C21") (pin "2") (pinfunction "2_2") (pintype "passive"))
      (node (ref "C22") (pin "2") (pinfunction "2_2") (pintype "passive"))
      (node (ref "C23") (pin "K") (pinfunction "K_K") (pintype "passive"))
      (node (ref "C24") (pin "1") (pinfunction "1_1") (pintype "passive"))
      (node (ref "DZ1") (pin "1") (pinfunction "A_1") (pintype "passive"))
      (node (ref "E2") (pin "K") (pinfunction "K_K") (pintype "passive"))
      (node (ref "J2") (pin "4") (pinfunction "GND_4") (pintype "passive"))
      (node (ref "RJ1") (pin "5") (pinfunction "NC_5") (pintype "passive"))
      (node (ref "RJ1") (pin "6") (pinfunction "RX-_6") (pintype "passive"))
      (node (ref "RJ1") (pin "7") (pinfunction "NC_7") (pintype "passive"))
      (node (ref "U1") (pin "5") (pinfunction "GND_5") (pintype "power_in"))
      (node (ref "U1") (pin "7") (pinfunction "REFEN_7") (pintype "input"))
      (node (ref "V1") (pin "1") (pinfunction "GND_1") (pintype "passive"))
    )
    (net (code "47") (name "Net-(J1-A)") (class "Default")
      (node (ref "J1") (pin "1") (pinfunction "A_1") (pintype "passive"))
      (node (ref "R10") (pin "2") (pinfunction "2_2") (pintype "passive"))
    )
    (net (code "48") (name "Net-(J2-A)") (class "Default")
      (node (ref "J2") (pin "1") (pinfunction "A_1") (pintype "passive"))
      (node (ref "R11") (pin "2") (pinfunction "2_2") (pintype "passive"))
    )
    (net (code "49") (name "Net-(J2-OUT)") (class "Default")
      (node (ref "J2") (pin "5") (pinfunction "OUT_5") (pintype "passive"))
      (node (ref "R12") (pin "1") (pinfunction "1_1") (pintype "passive"))
    )
    (net (code "50") (name "Net-(J3-A)") (class "Default")
      (node (ref "J3") (pin "1") (pinfunction "A_1") (pintype "passive"))
      (node (ref "R13") (pin "1") (pinfunction "1_1") (pintype "passive"))
      (node (ref "VD1") (pin "2") (pinfunction "K_2") (pintype "passive"))
    )
    (net (code "51") (name "Net-(J4-A)") (class "Default")
      (node (ref "J4") (pin "1") (pinfunction "A_1") (pintype "passive"))
      (node (ref "R14") (pin "1") (pinfunction "1_1") (pintype "passive"))
      (node (ref "VD2") (pin "2") (pinfunction "K_2") (pintype "passive"))
    )
    (net (code "52") (name "Net-(J5-A)") (class "Default")
      (node (ref "J5") (pin "1") (pinfunction "A_1") (pintype "passive"))
      (node (ref "R15") (pin "1") (pinfunction "1_1") (pintype "passive"))
      (node (ref "VD3") (pin "2") (pinfunction "K_2") (pintype "passive"))
    )
    (net (code "53") (name "Net-(J6-A6_DP1D+)") (class "Default")
      (node (ref "J6") (pin "13") (pinfunction "B6_DP2_D+_13") (pintype "passive"))
      (node (ref "J6") (pin "4") (pinfunction "A6_DP1D+_4") (pintype "passive"))
      (node (ref "R18") (pin "2") (pinfunction "2_2") (pintype "passive"))
    )
    (net (code "54") (name "Net-(J6-A7_DN1D-)") (class "Default")
      (node (ref "J6") (pin "12") (pinfunction "B7_DN2_D-_12") (pintype "passive"))
      (node (ref "J6") (pin "5") (pinfunction "A7_DN1D-_5") (pintype "passive"))
      (node (ref "R17") (pin "2") (pinfunction "2_2") (pintype "passive"))
    )
    (net (code "55") (name "Net-(U1-PWM)") (class "Default")
      (node (ref "R12") (pin "2") (pinfunction "2_2") (pintype "passive"))
      (node (ref "U1") (pin "3") (pinfunction "PWM_3") (pintype "input"))
    )
    (net (code "56") (name "Net-(U1-VCC)") (class "Default")
      (node (ref "C17") (pin "1") (pinfunction "1_1") (pintype "passive"))
      (node (ref "C20") (pin "1") (pinfunction "1_1") (pintype "passive"))
      (node (ref "L2") (pin "1") (pinfunction "1_1") (pintype "passive"))
      (node (ref "U1") (pin "8") (pinfunction "VCC_8") (pintype "input"))
    )
    (net (code "57") (name "Net-(U1-VOUT)") (class "Default")
      (node (ref "C19") (pin "1") (pinfunction "1_1") (pintype "passive"))
      (node (ref "L1") (pin "1") (pinfunction "1_1") (pintype "passive"))
      (node (ref "U1") (pin "6") (pinfunction "VOUT_6") (pintype "output"))
    )
    (net (code "58") (name "Net-(U2A-PB2{slash}BOOT1)") (class "Default")
      (node (ref "R19") (pin "1") (pinfunction "1_1") (pintype "passive"))
      (node (ref "U2") (pin "37") (pinfunction "PB2/BOOT1_37") (pintype "bidirectional"))
    )
    (net (code "59") (name "Net-(U2B-BOOT0)") (class "Default")
      (node (ref "R5") (pin "1") (pinfunction "1_1") (pintype "passive"))
      (node (ref "U2") (pin "94") (pinfunction "BOOT0_94") (pintype "input"))
    )
    (net (code "60") (name "Net-(U2B-NRST)") (class "Default")
      (node (ref "C32") (pin "1") (pinfunction "1_1") (pintype "passive"))
      (node (ref "SW1") (pin "1") (pinfunction "1_1") (pintype "passive"))
      (node (ref "SW1") (pin "4") (pinfunction "4_4") (pintype "passive"))
      (node (ref "U2") (pin "14") (pinfunction "NRST_14") (pintype "bidirectional"))
    )
    (net (code "61") (name "Net-(U2B-PH0{slash}OSC_IN)") (class "Default")
      (node (ref "C29") (pin "1") (pinfunction "1_1") (pintype "passive"))
      (node (ref "U2") (pin "12") (pinfunction "PH0/OSC_IN_12") (pintype "bidirectional"))
      (node (ref "X1") (pin "3") (pinfunction "3_3") (pintype "passive"))
    )
    (net (code "62") (name "Net-(U2B-PH1{slash}OSC_OUT)") (class "Default")
      (node (ref "C35") (pin "1") (pinfunction "1_1") (pintype "passive"))
      (node (ref "U2") (pin "13") (pinfunction "PH1/OSC_OUT_13") (pintype "bidirectional"))
      (node (ref "X1") (pin "1") (pinfunction "1_1") (pintype "passive"))
    )
    (net (code "63") (name "Net-(U2C-VCAP_1)") (class "Default")
      (node (ref "C28") (pin "2") (pinfunction "2_2") (pintype "passive"))
      (node (ref "U2") (pin "49") (pinfunction "VCAP_1_49") (pintype "power_in"))
    )
    (net (code "64") (name "Net-(U2C-VCAP_2)") (class "Default")
      (node (ref "C25") (pin "2") (pinfunction "2_2") (pintype "passive"))
      (node (ref "U2") (pin "73") (pinfunction "VCAP_2_73") (pintype "power_in"))
    )
    (net (code "65") (name "Net-(V1-Vin)") (class "Default")
      (node (ref "C16") (pin "1") (pinfunction "1_1") (pintype "passive"))
      (node (ref "C18") (pin "A") (pinfunction "A_A") (pintype "passive"))
      (node (ref "R16") (pin "1") (pinfunction "1_1") (pintype "passive"))
      (node (ref "V1") (pin "3") (pinfunction "Vin_3") (pintype "passive"))
    )
    (net (code "66") (name "VCC+12") (class "Default")
      (node (ref "C23") (pin "A") (pinfunction "A_A") (pintype "passive"))
      (node (ref "R16") (pin "2") (pinfunction "2_2") (pintype "passive"))
      (node (ref "RJ1") (pin "3") (pinfunction "RX+_3") (pintype "passive"))
    )
    (net (code "67") (name "VDD+24") (class "Default")
      (node (ref "C15") (pin "1") (pinfunction "1_1") (pintype "passive"))
      (node (ref "J1") (pin "6") (pinfunction "VCC_6") (pintype "passive"))
      (node (ref "RJ1") (pin "1") (pinfunction "TX+_1") (pintype "passive"))
    )
    (net (code "68") (name "unconnected-(J6-A5_CC1-Pad3)") (class "Default")
      (node (ref "J6") (pin "3") (pinfunction "A5_CC1_3") (pintype "passive"))
    )
    (net (code "69") (name "unconnected-(J6-A8_SBU1-Pad6)") (class "Default")
      (node (ref "J6") (pin "6") (pinfunction "A8_SBU1_6") (pintype "passive"))
    )
    (net (code "70") (name "unconnected-(J6-B5_CC2-Pad14)") (class "Default")
      (node (ref "J6") (pin "14") (pinfunction "B5_CC2_14") (pintype "passive"))
    )
    (net (code "71") (name "unconnected-(J6-B8_SBU2-Pad11)") (class "Default")
      (node (ref "J6") (pin "11") (pinfunction "B8_SBU2_11") (pintype "passive"))
    )
    (net (code "72") (name "unconnected-(U1-ENB-Pad4)") (class "Default")
      (node (ref "U1") (pin "4") (pinfunction "ENB_4") (pintype "input+no_connect"))
    )
    (net (code "73") (name "unconnected-(U1-NC-Pad1)") (class "Default")
      (node (ref "U1") (pin "1") (pinfunction "NC_1") (pintype "power_in+no_connect"))
    )
    (net (code "74") (name "unconnected-(U1-NC-Pad2)") (class "Default")
      (node (ref "U1") (pin "2") (pinfunction "NC_2") (pintype "power_in+no_connect"))
    )
    (net (code "75") (name "unconnected-(U2A-PA3-Pad26)") (class "Default")
      (node (ref "U2") (pin "26") (pinfunction "PA3_26") (pintype "bidirectional+no_connect"))
    )
    (net (code "76") (name "unconnected-(U2A-PA8-Pad67)") (class "Default")
      (node (ref "U2") (pin "67") (pinfunction "PA8_67") (pintype "bidirectional+no_connect"))
    )
    (net (code "77") (name "unconnected-(U2A-PA9-Pad68)") (class "Default")
      (node (ref "U2") (pin "68") (pinfunction "PA9_68") (pintype "bidirectional+no_connect"))
    )
    (net (code "78") (name "unconnected-(U2A-PA10-Pad69)") (class "Default")
      (node (ref "U2") (pin "69") (pinfunction "PA10_69") (pintype "bidirectional+no_connect"))
    )
    (net (code "79") (name "unconnected-(U2A-PA15-Pad77)") (class "Default")
      (node (ref "U2") (pin "77") (pinfunction "PA15_77") (pintype "bidirectional+no_connect"))
    )
    (net (code "80") (name "unconnected-(U2A-PB3-Pad89)") (class "Default")
      (node (ref "U2") (pin "89") (pinfunction "PB3_89") (pintype "bidirectional+no_connect"))
    )
    (net (code "81") (name "unconnected-(U2A-PB4-Pad90)") (class "Default")
      (node (ref "U2") (pin "90") (pinfunction "PB4_90") (pintype "bidirectional+no_connect"))
    )
    (net (code "82") (name "unconnected-(U2A-PB5-Pad91)") (class "Default")
      (node (ref "U2") (pin "91") (pinfunction "PB5_91") (pintype "bidirectional+no_connect"))
    )
    (net (code "83") (name "unconnected-(U2A-PB6-Pad92)") (class "Default")
      (node (ref "U2") (pin "92") (pinfunction "PB6_92") (pintype "bidirectional+no_connect"))
    )
    (net (code "84") (name "unconnected-(U2A-PB7-Pad93)") (class "Default")
      (node (ref "U2") (pin "93") (pinfunction "PB7_93") (pintype "bidirectional+no_connect"))
    )
    (net (code "85") (name "unconnected-(U2A-PB8-Pad95)") (class "Default")
      (node (ref "U2") (pin "95") (pinfunction "PB8_95") (pintype "bidirectional+no_connect"))
    )
    (net (code "86") (name "unconnected-(U2A-PB9-Pad96)") (class "Default")
      (node (ref "U2") (pin "96") (pinfunction "PB9_96") (pintype "bidirectional+no_connect"))
    )
    (net (code "87") (name "unconnected-(U2A-PB10-Pad47)") (class "Default")
      (node (ref "U2") (pin "47") (pinfunction "PB10_47") (pintype "bidirectional+no_connect"))
    )
    (net (code "88") (name "unconnected-(U2A-PB11-Pad48)") (class "Default")
      (node (ref "U2") (pin "48") (pinfunction "PB11_48") (pintype "bidirectional+no_connect"))
    )
    (net (code "89") (name "unconnected-(U2A-PC0-Pad15)") (class "Default")
      (node (ref "U2") (pin "15") (pinfunction "PC0_15") (pintype "bidirectional+no_connect"))
    )
    (net (code "90") (name "unconnected-(U2A-PC3-Pad18)") (class "Default")
      (node (ref "U2") (pin "18") (pinfunction "PC3_18") (pintype "bidirectional+no_connect"))
    )
    (net (code "91") (name "unconnected-(U2A-PC6-Pad63)") (class "Default")
      (node (ref "U2") (pin "63") (pinfunction "PC6_63") (pintype "bidirectional+no_connect"))
    )
    (net (code "92") (name "unconnected-(U2A-PC7-Pad64)") (class "Default")
      (node (ref "U2") (pin "64") (pinfunction "PC7_64") (pintype "bidirectional+no_connect"))
    )
    (net (code "93") (name "unconnected-(U2A-PC8-Pad65)") (class "Default")
      (node (ref "U2") (pin "65") (pinfunction "PC8_65") (pintype "bidirectional+no_connect"))
    )
    (net (code "94") (name "unconnected-(U2A-PC13-Pad7)") (class "Default")
      (node (ref "U2") (pin "7") (pinfunction "PC13_7") (pintype "bidirectional+no_connect"))
    )
    (net (code "95") (name "unconnected-(U2A-PC14{slash}OSC32_IN-Pad8)") (class "Default")
      (node (ref "U2") (pin "8") (pinfunction "PC14/OSC32_IN_8") (pintype "bidirectional"))
    )
    (net (code "96") (name "unconnected-(U2A-PC15{slash}OSC32_OUT-Pad9)") (class "Default")
      (node (ref "U2") (pin "9") (pinfunction "PC15/OSC32_OUT_9") (pintype "bidirectional"))
    )
    (net (code "97") (name "unconnected-(U2A-PD0-Pad81)") (class "Default")
      (node (ref "U2") (pin "81") (pinfunction "PD0_81") (pintype "bidirectional+no_connect"))
    )
    (net (code "98") (name "unconnected-(U2A-PD1-Pad82)") (class "Default")
      (node (ref "U2") (pin "82") (pinfunction "PD1_82") (pintype "bidirectional+no_connect"))
    )
    (net (code "99") (name "unconnected-(U2A-PD2-Pad83)") (class "Default")
      (node (ref "U2") (pin "83") (pinfunction "PD2_83") (pintype "bidirectional+no_connect"))
    )
    (net (code "100") (name "unconnected-(U2A-PD3-Pad84)") (class "Default")
      (node (ref "U2") (pin "84") (pinfunction "PD3_84") (pintype "bidirectional+no_connect"))
    )
    (net (code "101") (name "unconnected-(U2A-PD4-Pad85)") (class "Default")
      (node (ref "U2") (pin "85") (pinfunction "PD4_85") (pintype "bidirectional+no_connect"))
    )
    (net (code "102") (name "unconnected-(U2A-PD5-Pad86)") (class "Default")
      (node (ref "U2") (pin "86") (pinfunction "PD5_86") (pintype "bidirectional+no_connect"))
    )
    (net (code "103") (name "unconnected-(U2A-PD6-Pad87)") (class "Default")
      (node (ref "U2") (pin "87") (pinfunction "PD6_87") (pintype "bidirectional+no_connect"))
    )
    (net (code "104") (name "unconnected-(U2A-PD7-Pad88)") (class "Default")
      (node (ref "U2") (pin "88") (pinfunction "PD7_88") (pintype "bidirectional+no_connect"))
    )
    (net (code "105") (name "unconnected-(U2A-PD8-Pad55)") (class "Default")
      (node (ref "U2") (pin "55") (pinfunction "PD8_55") (pintype "bidirectional+no_connect"))
    )
    (net (code "106") (name "unconnected-(U2A-PD9-Pad56)") (class "Default")
      (node (ref "U2") (pin "56") (pinfunction "PD9_56") (pintype "bidirectional+no_connect"))
    )
    (net (code "107") (name "unconnected-(U2A-PD10-Pad57)") (class "Default")
      (node (ref "U2") (pin "57") (pinfunction "PD10_57") (pintype "bidirectional+no_connect"))
    )
    (net (code "108") (name "unconnected-(U2A-PD11-Pad58)") (class "Default")
      (node (ref "U2") (pin "58") (pinfunction "PD11_58") (pintype "bidirectional+no_connect"))
    )
    (net (code "109") (name "unconnected-(U2A-PD12-Pad59)") (class "Default")
      (node (ref "U2") (pin "59") (pinfunction "PD12_59") (pintype "bidirectional+no_connect"))
    )
    (net (code "110") (name "unconnected-(U2A-PD13-Pad60)") (class "Default")
      (node (ref "U2") (pin "60") (pinfunction "PD13_60") (pintype "bidirectional+no_connect"))
    )
    (net (code "111") (name "unconnected-(U2A-PD14-Pad61)") (class "Default")
      (node (ref "U2") (pin "61") (pinfunction "PD14_61") (pintype "bidirectional+no_connect"))
    )
    (net (code "112") (name "unconnected-(U2A-PD15-Pad62)") (class "Default")
      (node (ref "U2") (pin "62") (pinfunction "PD15_62") (pintype "bidirectional+no_connect"))
    )
    (net (code "113") (name "unconnected-(U2B-PE2-Pad1)") (class "Default")
      (node (ref "U2") (pin "1") (pinfunction "PE2_1") (pintype "bidirectional+no_connect"))
    )
    (net (code "114") (name "unconnected-(U2B-PE4-Pad3)") (class "Default")
      (node (ref "U2") (pin "3") (pinfunction "PE4_3") (pintype "bidirectional+no_connect"))
    )
    (net (code "115") (name "unconnected-(U2B-PE5-Pad4)") (class "Default")
      (node (ref "U2") (pin "4") (pinfunction "PE5_4") (pintype "bidirectional+no_connect"))
    )
    (net (code "116") (name "unconnected-(U2B-PE6-Pad5)") (class "Default")
      (node (ref "U2") (pin "5") (pinfunction "PE6_5") (pintype "bidirectional+no_connect"))
    )
    (net (code "117") (name "unconnected-(U2B-PE7-Pad38)") (class "Default")
      (node (ref "U2") (pin "38") (pinfunction "PE7_38") (pintype "bidirectional+no_connect"))
    )
    (net (code "118") (name "unconnected-(U2B-PE8-Pad39)") (class "Default")
      (node (ref "U2") (pin "39") (pinfunction "PE8_39") (pintype "bidirectional+no_connect"))
    )
    (net (code "119") (name "unconnected-(U2B-PE10-Pad41)") (class "Default")
      (node (ref "U2") (pin "41") (pinfunction "PE10_41") (pintype "bidirectional"))
    )
    (net (code "120") (name "unconnected-(U2B-PE12-Pad43)") (class "Default")
      (node (ref "U2") (pin "43") (pinfunction "PE12_43") (pintype "bidirectional+no_connect"))
    )
    (net (code "121") (name "unconnected-(U2B-PE13-Pad44)") (class "Default")
      (node (ref "U2") (pin "44") (pinfunction "PE13_44") (pintype "bidirectional+no_connect"))
    )
    (net (code "122") (name "unconnected-(U2B-PE14-Pad45)") (class "Default")
      (node (ref "U2") (pin "45") (pinfunction "PE14_45") (pintype "bidirectional+no_connect"))
    )
    (net (code "123") (name "unconnected-(U2B-PE15-Pad46)") (class "Default")
      (node (ref "U2") (pin "46") (pinfunction "PE15_46") (pintype "bidirectional+no_connect"))
    )
  )
)
